# RS485.net
KiCad netlist of a schematic drawn in Altium Designer
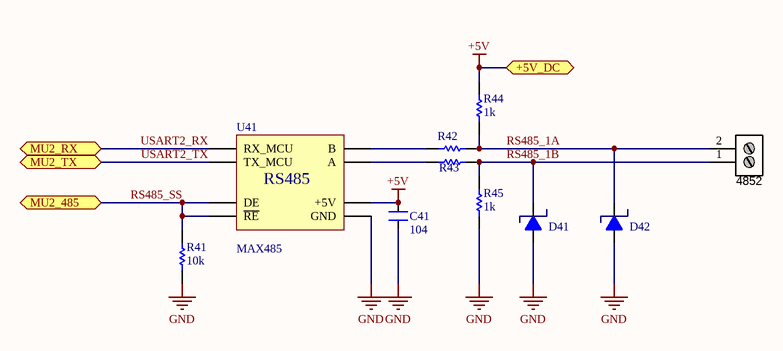
[diagram p0: RS485.SchDoc]

(export (version "E")
  (design (tool "Eeschema 10.0.6"))
  (components
    (comp (ref "4852")
      (value "GreHed")
      (footprint "2P_PCB1")
      (description "Terminal Block Screw Type THT 2-Position 3.81mm pitch")
      (libsource (lib "PBL - Connectors") (part "2P_ScrewTerm_90S_3.81MM"))
    )
    (comp (ref "C41")
      (value "104")
      (footprint "CAPC2012N_F")
      (fields (field (name "Comment") "Cap_104_0805"))
      (libsource (lib "Tuan") (part "CAP NP"))
    )
    (comp (ref "D41")
      (value "TVS Diodes")
      (footprint "DO-214AA")
      (description "TVS Diodes - Transient Voltage Suppressors")
      (libsource (lib "Tuan") (part "TVS Diodes"))
    )
    (comp (ref "D42")
      (value "TVS Diodes")
      (footprint "DO-214AA")
      (description "TVS Diodes - Transient Voltage Suppressors")
      (libsource (lib "Tuan") (part "TVS Diodes"))
    )
    (comp (ref "R41")
      (value "10k")
      (footprint "RESC1608N_F")
      (fields (field (name "Comment") "Res_10k_0603"))
      (libsource (lib "Tuan") (part "Res"))
    )
    (comp (ref "R42") (value "Res_10R_0805") (footprint "RESC2012N_F") (libsource (lib "Tuan") (part "Res")))
    (comp (ref "R43") (value "Res_10R_0805") (footprint "RESC2012N_F") (libsource (lib "Tuan") (part "Res")))
    (comp (ref "R44")
      (value "1k")
      (footprint "RESC1608N_F")
      (fields (field (name "Comment") "Res_1k_0603"))
      (libsource (lib "Tuan") (part "Res"))
    )
    (comp (ref "R45")
      (value "1k")
      (footprint "RESC1608N_F")
      (fields (field (name "Comment") "Res_1k_0603"))
      (libsource (lib "Tuan") (part "Res"))
    )
    (comp (ref "U41")
      (value "MAX4858 chân cắm")
      (footprint "SOIC 8")
      (description "RS485")
      (fields (field (name "VL2") "MAX485"))
      (libsource (lib "Tuan") (part "485"))
    )
  )
  (nets
    (net (code "1") (name "+5V") (class "Default")
      (node (ref "C41") (pin "1") (pinfunction "1_1") (pintype "passive"))
      (node (ref "R44") (pin "2") (pinfunction "2_2") (pintype "passive"))
      (node (ref "U41") (pin "8") (pinfunction "+5V_8") (pintype "passive"))
    )
    (net (code "2") (name "/RS485_1A") (class "Default")
      (node (ref "4852") (pin "2") (pinfunction "2_2") (pintype "passive"))
      (node (ref "D42") (pin "K") (pinfunction "K_K") (pintype "passive"))
      (node (ref "R42") (pin "2") (pinfunction "2_2") (pintype "passive"))
      (node (ref "R44") (pin "1") (pinfunction "1_1") (pintype "passive"))
    )
    (net (code "3") (name "/RS485_1B") (class "Default")
      (node (ref "4852") (pin "1") (pinfunction "1_1") (pintype "passive"))
      (node (ref "D41") (pin "K") (pinfunction "K_K") (pintype "passive"))
      (node (ref "R43") (pin "2") (pinfunction "2_2") (pintype "passive"))
      (node (ref "R45") (pin "2") (pinfunction "2_2") (pintype "passive"))
    )
    (net (code "4") (name "/RS485_SS") (class "Default")
      (node (ref "R41") (pin "2") (pinfunction "2_2") (pintype "passive"))
      (node (ref "U41") (pin "2") (pinfunction "~{RE}_2") (pintype "passive"))
      (node (ref "U41") (pin "3") (pinfunction "DE_3") (pintype "passive"))
    )
    (net (code "5") (name "/USART2_RX") (class "Default")
      (node (ref "U41") (pin "1") (pinfunction "RX_MCU_1") (pintype "passive"))
    )
    (net (code "6") (name "/USART2_TX") (class "Default")
      (node (ref "U41") (pin "4") (pinfunction "TX_MCU_4") (pintype "passive"))
    )
    (net (code "7") (name "GND") (class "Default")
      (node (ref "C41") (pin "2") (pinfunction "2_2") (pintype "passive"))
      (node (ref "D41") (pin "A") (pinfunction "A_A") (pintype "passive"))
      (node (ref "D42") (pin "A") (pinfunction "A_A") (pintype "passive"))
      (node (ref "R41") (pin "1") (pinfunction "1_1") (pintype "passive"))
      (node (ref "R45") (pin "1") (pinfunction "1_1") (pintype "passive"))
      (node (ref "U41") (pin "5") (pinfunction "GND_5") (pintype "passive"))
    )
    (net (code "8") (name "Net-(U41-A)") (class "Default")
      (node (ref "R43") (pin "1") (pinfunction "1_1") (pintype "passive"))
      (node (ref "U41") (pin "6") (pinfunction "A_6") (pintype "passive"))
    )
    (net (code "9") (name "Net-(U41-B)") (class "Default")
      (node (ref "R42") (pin "1") (pinfunction "1_1") (pintype "passive"))
      (node (ref "U41") (pin "7") (pinfunction "B_7") (pintype "passive"))
    )
  )
)
